# Muller-C2.net
KiCad netlist of a schematic drawn in Altium Designer
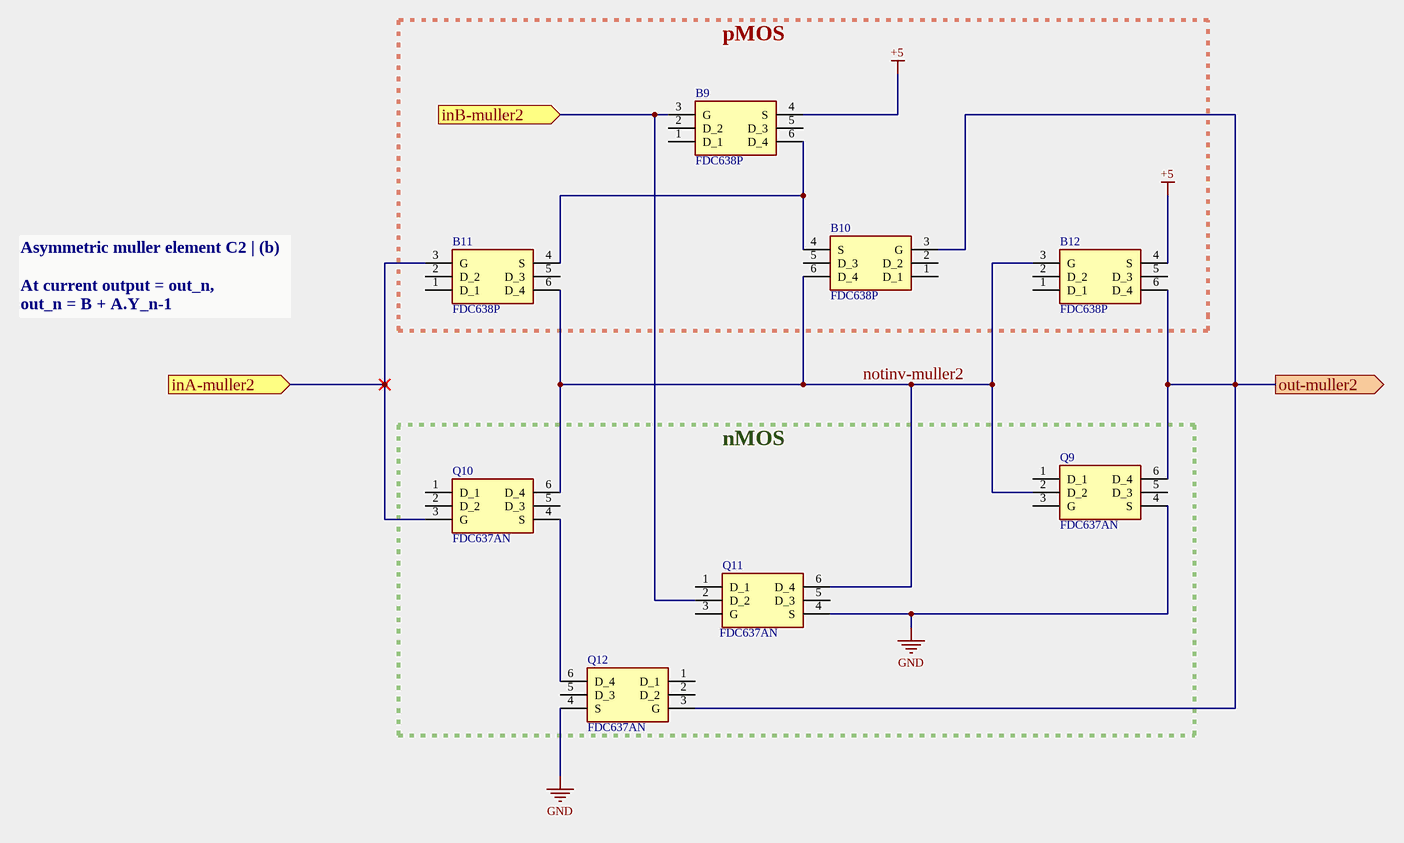
[diagram p0: Muller-C2.SchDoc]

(export (version "E")
  (design (tool "Eeschema 10.0.6"))
  (components
    (comp (ref "B9")
      (value "FDC638P")
      (footprint "SOT95P275X110-6N")
      (description "Low gate charge (10 nC typical)")
      (fields (field (name "MOUSER PART NUMBER") "512-FDC638P"))
      (libsource (lib "iloke") (part "FDC638P"))
    )
    (comp (ref "B10")
      (value "FDC638P")
      (footprint "SOT95P275X110-6N")
      (description "Low gate charge (10 nC typical)")
      (fields (field (name "MOUSER PART NUMBER") "512-FDC638P"))
      (libsource (lib "") (part "FDC638P_1"))
    )
    (comp (ref "B11")
      (value "FDC638P")
      (footprint "SOT95P275X110-6N")
      (description "Low gate charge (10 nC typical)")
      (fields (field (name "MOUSER PART NUMBER") "512-FDC638P"))
      (libsource (lib "iloke") (part "FDC638P"))
    )
    (comp (ref "B12")
      (value "FDC638P")
      (footprint "SOT95P275X110-6N")
      (description "Low gate charge (10 nC typical)")
      (fields (field (name "MOUSER PART NUMBER") "512-FDC638P"))
      (libsource (lib "iloke") (part "FDC638P"))
    )
    (comp (ref "Q9")
      (value "FDC637AN")
      (footprint "SOT95P275X110-6N")
      (description "Low gate charge (10.5nC typical).")
      (fields (field (name "MOUSER PART NUMBER") "512-FDC637AN"))
      (libsource (lib "iloke") (part "FDC637AN"))
    )
    (comp (ref "Q10")
      (value "FDC637AN")
      (footprint "SOT95P275X110-6N")
      (description "Low gate charge (10.5nC typical).")
      (fields (field (name "MOUSER PART NUMBER") "512-FDC637AN"))
      (libsource (lib "iloke") (part "FDC637AN"))
    )
    (comp (ref "Q11")
      (value "FDC637AN")
      (footprint "SOT95P275X110-6N")
      (description "Low gate charge (10.5nC typical).")
      (fields (field (name "MOUSER PART NUMBER") "512-FDC637AN"))
      (libsource (lib "iloke") (part "FDC637AN"))
    )
    (comp (ref "Q12")
      (value "FDC637AN")
      (footprint "SOT95P275X110-6N")
      (description "Low gate charge (10.5nC typical).")
      (fields (field (name "MOUSER PART NUMBER") "512-FDC637AN"))
      (libsource (lib "") (part "FDC637AN_1"))
    )
  )
  (nets
    (net (code "1") (name "+5") (class "Default")
      (node (ref "B12") (pin "4") (pinfunction "S_4") (pintype "passive"))
      (node (ref "B9") (pin "4") (pinfunction "S_4") (pintype "passive"))
    )
    (net (code "2") (name "/inA-muller2") (class "Default")
      (node (ref "B11") (pin "3") (pinfunction "G_3") (pintype "passive"))
      (node (ref "Q10") (pin "3") (pinfunction "G_3") (pintype "passive"))
    )
    (net (code "3") (name "/inB-muller2") (class "Default")
      (node (ref "B9") (pin "3") (pinfunction "G_3") (pintype "passive"))
      (node (ref "Q11") (pin "2") (pinfunction "D_2_2") (pintype "passive"))
    )
    (net (code "4") (name "/notinv-muller2") (class "Default")
      (node (ref "B10") (pin "6") (pinfunction "D_4_6") (pintype "passive"))
      (node (ref "B11") (pin "6") (pinfunction "D_4_6") (pintype "passive"))
      (node (ref "B12") (pin "3") (pinfunction "G_3") (pintype "passive"))
      (node (ref "Q10") (pin "6") (pinfunction "D_4_6") (pintype "passive"))
      (node (ref "Q11") (pin "6") (pinfunction "D_4_6") (pintype "passive"))
      (node (ref "Q9") (pin "2") (pinfunction "D_2_2") (pintype "passive"))
    )
    (net (code "5") (name "/out-muller2") (class "Default")
      (node (ref "B10") (pin "3") (pinfunction "G_3") (pintype "passive"))
      (node (ref "B12") (pin "6") (pinfunction "D_4_6") (pintype "passive"))
      (node (ref "Q12") (pin "3") (pinfunction "G_3") (pintype "passive"))
      (node (ref "Q9") (pin "6") (pinfunction "D_4_6") (pintype "passive"))
    )
    (net (code "6") (name "GND") (class "Default")
      (node (ref "Q11") (pin "4") (pinfunction "S_4") (pintype "passive"))
      (node (ref "Q12") (pin "4") (pinfunction "S_4") (pintype "passive"))
      (node (ref "Q9") (pin "4") (pinfunction "S_4") (pintype "passive"))
    )
    (net (code "7") (name "Net-(B10-S)") (class "Default")
      (node (ref "B10") (pin "4") (pinfunction "S_4") (pintype "passive"))
      (node (ref "B11") (pin "4") (pinfunction "S_4") (pintype "passive"))
      (node (ref "B9") (pin "6") (pinfunction "D_4_6") (pintype "passive"))
    )
    (net (code "8") (name "Net-(Q10-S)") (class "Default")
      (node (ref "Q10") (pin "4") (pinfunction "S_4") (pintype "passive"))
      (node (ref "Q12") (pin "6") (pinfunction "D_4_6") (pintype "passive"))
    )
    (net (code "9") (name "unconnected-(B9-D_1-Pad1)") (class "Default")
      (node (ref "B9") (pin "1") (pinfunction "D_1_1") (pintype "passive"))
    )
    (net (code "10") (name "unconnected-(B9-D_2-Pad2)") (class "Default")
      (node (ref "B9") (pin "2") (pinfunction "D_2_2") (pintype "passive"))
    )
    (net (code "11") (name "unconnected-(B9-D_3-Pad5)") (class "Default")
      (node (ref "B9") (pin "5") (pinfunction "D_3_5") (pintype "passive"))
    )
    (net (code "12") (name "unconnected-(B10-D_1-Pad1)") (class "Default")
      (node (ref "B10") (pin "1") (pinfunction "D_1_1") (pintype "passive"))
    )
    (net (code "13") (name "unconnected-(B10-D_2-Pad2)") (class "Default")
      (node (ref "B10") (pin "2") (pinfunction "D_2_2") (pintype "passive"))
    )
    (net (code "14") (name "unconnected-(B10-D_3-Pad5)") (class "Default")
      (node (ref "B10") (pin "5") (pinfunction "D_3_5") (pintype "passive"))
    )
    (net (code "15") (name "unconnected-(B11-D_1-Pad1)") (class "Default")
      (node (ref "B11") (pin "1") (pinfunction "D_1_1") (pintype "passive"))
    )
    (net (code "16") (name "unconnected-(B11-D_2-Pad2)") (class "Default")
      (node (ref "B11") (pin "2") (pinfunction "D_2_2") (pintype "passive"))
    )
    (net (code "17") (name "unconnected-(B11-D_3-Pad5)") (class "Default")
      (node (ref "B11") (pin "5") (pinfunction "D_3_5") (pintype "passive"))
    )
    (net (code "18") (name "unconnected-(B12-D_1-Pad1)") (class "Default")
      (node (ref "B12") (pin "1") (pinfunction "D_1_1") (pintype "passive"))
    )
    (net (code "19") (name "unconnected-(B12-D_2-Pad2)") (class "Default")
      (node (ref "B12") (pin "2") (pinfunction "D_2_2") (pintype "passive"))
    )
    (net (code "20") (name "unconnected-(B12-D_3-Pad5)") (class "Default")
      (node (ref "B12") (pin "5") (pinfunction "D_3_5") (pintype "passive"))
    )
    (net (code "21") (name "unconnected-(Q9-D_1-Pad1)") (class "Default")
      (node (ref "Q9") (pin "1") (pinfunction "D_1_1") (pintype "passive"))
    )
    (net (code "22") (name "unconnected-(Q9-D_3-Pad5)") (class "Default")
      (node (ref "Q9") (pin "5") (pinfunction "D_3_5") (pintype "passive"))
    )
    (net (code "23") (name "unconnected-(Q9-G-Pad3)") (class "Default")
      (node (ref "Q9") (pin "3") (pinfunction "G_3") (pintype "passive"))
    )
    (net (code "24") (name "unconnected-(Q10-D_1-Pad1)") (class "Default")
      (node (ref "Q10") (pin "1") (pinfunction "D_1_1") (pintype "passive"))
    )
    (net (code "25") (name "unconnected-(Q10-D_2-Pad2)") (class "Default")
      (node (ref "Q10") (pin "2") (pinfunction "D_2_2") (pintype "passive"))
    )
    (net (code "26") (name "unconnected-(Q10-D_3-Pad5)") (class "Default")
      (node (ref "Q10") (pin "5") (pinfunction "D_3_5") (pintype "passive"))
    )
    (net (code "27") (name "unconnected-(Q11-D_1-Pad1)") (class "Default")
      (node (ref "Q11") (pin "1") (pinfunction "D_1_1") (pintype "passive"))
    )
    (net (code "28") (name "unconnected-(Q11-D_3-Pad5)") (class "Default")
      (node (ref "Q11") (pin "5") (pinfunction "D_3_5") (pintype "passive"))
    )
    (net (code "29") (name "unconnected-(Q11-G-Pad3)") (class "Default")
      (node (ref "Q11") (pin "3") (pinfunction "G_3") (pintype "passive"))
    )
    (net (code "30") (name "unconnected-(Q12-D_1-Pad1)") (class "Default")
      (node (ref "Q12") (pin "1") (pinfunction "D_1_1") (pintype "passive"))
    )
    (net (code "31") (name "unconnected-(Q12-D_2-Pad2)") (class "Default")
      (node (ref "Q12") (pin "2") (pinfunction "D_2_2") (pintype "passive"))
    )
    (net (code "32") (name "unconnected-(Q12-D_3-Pad5)") (class "Default")
      (node (ref "Q12") (pin "5") (pinfunction "D_3_5") (pintype "passive"))
    )
  )
)
